# SCH_MicrowaveResistiveKeyb_2025-11-10.net
KiCad netlist of a schematic drawn in EasyEDA
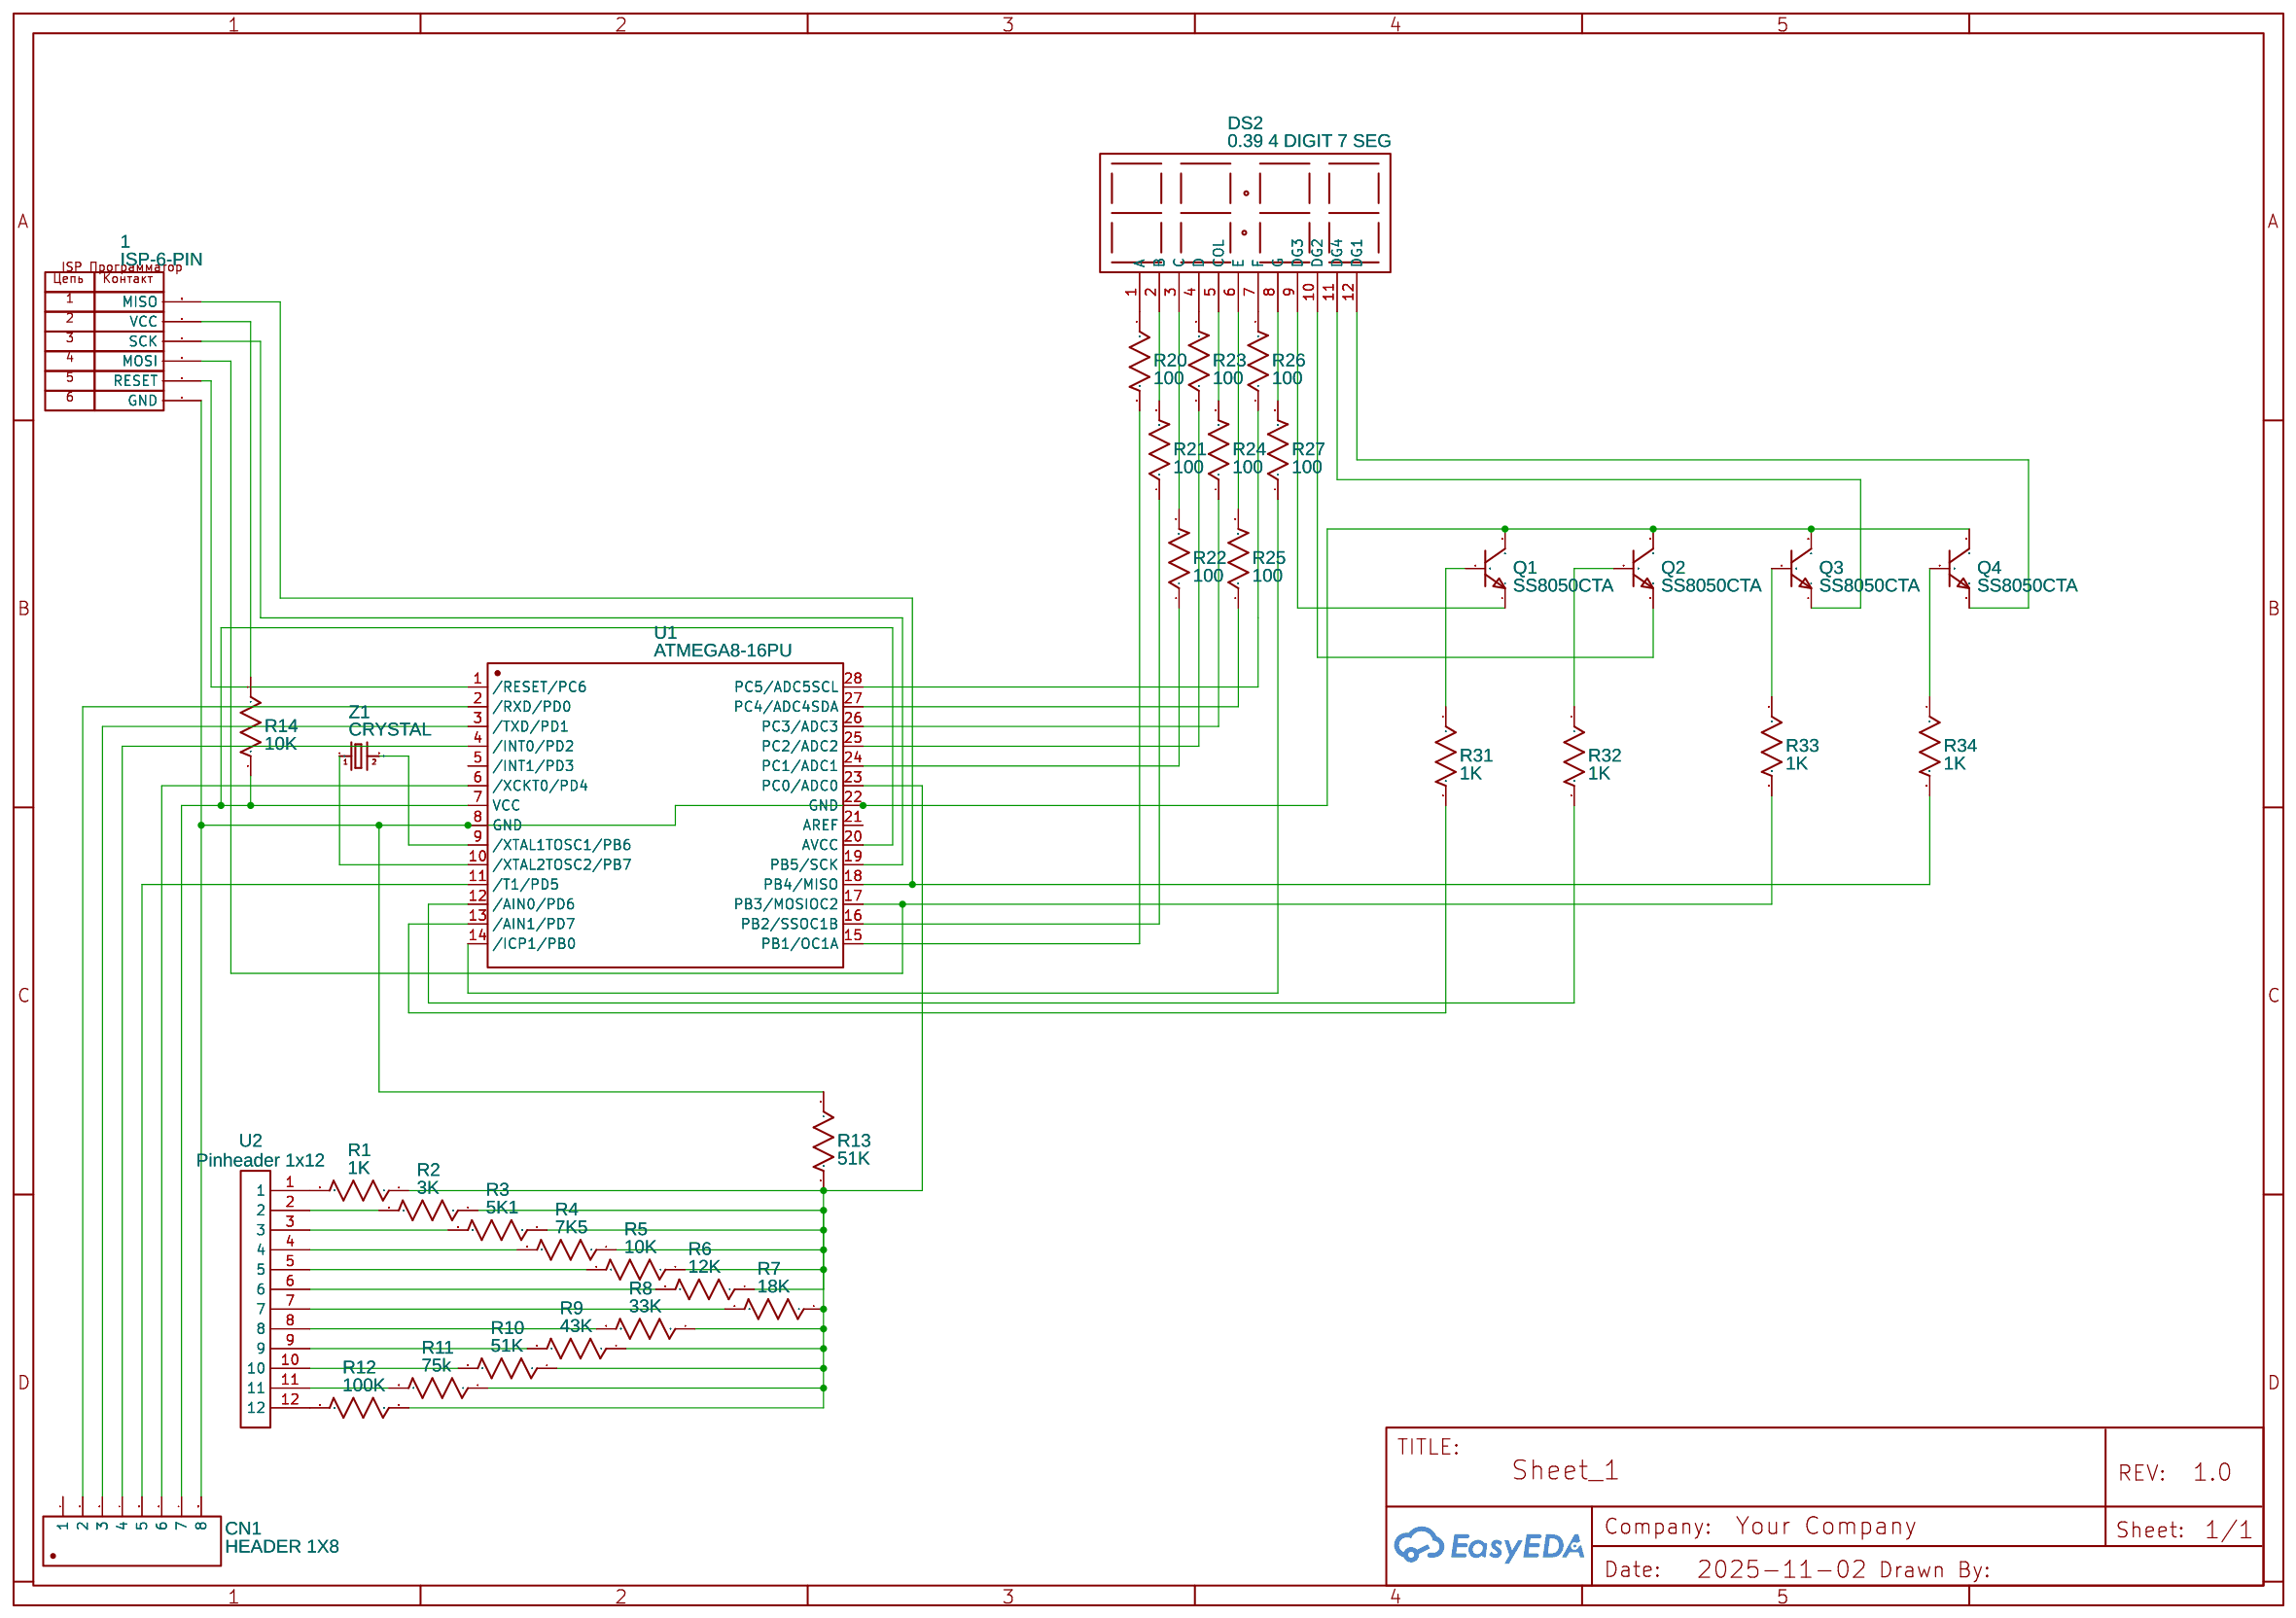
[diagram p0: schematic sheet]

(export (version "E")
  (design (tool "Eeschema 10.0.6"))
  (components
    (comp (ref "1") (value "ISP-6-PIN") (libsource (lib "") (part "ISP-6-PIN")))
    (comp (ref "CN1") (value "HEADER 1X8") (libsource (lib "") (part "HEADER 1X8")))
    (comp (ref "DS2")
      (value "0.39 4 DIGIT 7 SEG")
      (fields
        (field (name "Manufacturer Part") "0.39 Inch 4 Digit Common Anode 7 Segment Display Clock")
        (field (name "Manufacturer") "TAKAMISAWA")
      )
      (libsource (lib "") (part "0.39 4 DIGIT 7 SEG"))
    )
    (comp (ref "Q1")
      (value "SS8050CTA")
      (fields (field (name "Manufacturer") "onsemi(安森美)"))
      (libsource (lib "") (part "SS8050CTA"))
    )
    (comp (ref "Q2")
      (value "SS8050CTA")
      (fields (field (name "Manufacturer") "onsemi(安森美)"))
      (libsource (lib "") (part "SS8050CTA"))
    )
    (comp (ref "Q3")
      (value "SS8050CTA")
      (fields (field (name "Manufacturer") "onsemi(安森美)"))
      (libsource (lib "") (part "SS8050CTA"))
    )
    (comp (ref "Q4")
      (value "SS8050CTA")
      (fields (field (name "Manufacturer") "onsemi(安森美)"))
      (libsource (lib "") (part "SS8050CTA"))
    )
    (comp (ref "R1") (value "1K") (libsource (lib "") (part "CRCW060323K2FKEA")))
    (comp (ref "R2") (value "3K") (libsource (lib "") (part "CRCW060323K2FKEA")))
    (comp (ref "R3") (value "5K1") (libsource (lib "") (part "CRCW060323K2FKEA")))
    (comp (ref "R4") (value "7K5") (libsource (lib "") (part "CRCW060323K2FKEA")))
    (comp (ref "R5") (value "10K") (libsource (lib "") (part "CRCW060323K2FKEA")))
    (comp (ref "R6") (value "12K") (libsource (lib "") (part "CRCW060323K2FKEA")))
    (comp (ref "R7") (value "18K") (libsource (lib "") (part "CRCW060323K2FKEA")))
    (comp (ref "R8") (value "33K") (libsource (lib "") (part "CRCW060323K2FKEA")))
    (comp (ref "R9") (value "43K") (libsource (lib "") (part "CRCW060323K2FKEA")))
    (comp (ref "R10") (value "51K") (libsource (lib "") (part "CRCW060323K2FKEA")))
    (comp (ref "R11") (value "75k") (libsource (lib "") (part "CRCW060323K2FKEA")))
    (comp (ref "R12") (value "100K") (libsource (lib "") (part "CRCW060323K2FKEA")))
    (comp (ref "R13") (value "51K") (libsource (lib "") (part "CRCW060323K2FKEA_2")))
    (comp (ref "R14") (value "10K") (libsource (lib "") (part "CRCW060323K2FKEA_2")))
    (comp (ref "R20") (value "100") (libsource (lib "") (part "CRCW060323K2FKEA_2")))
    (comp (ref "R21") (value "100") (libsource (lib "") (part "CRCW060323K2FKEA_1")))
    (comp (ref "R22") (value "100") (libsource (lib "") (part "CRCW060323K2FKEA_1")))
    (comp (ref "R23") (value "100") (libsource (lib "") (part "CRCW060323K2FKEA_1")))
    (comp (ref "R24") (value "100") (libsource (lib "") (part "CRCW060323K2FKEA_1")))
    (comp (ref "R25") (value "100") (libsource (lib "") (part "CRCW060323K2FKEA_1")))
    (comp (ref "R26") (value "100") (libsource (lib "") (part "CRCW060323K2FKEA_1")))
    (comp (ref "R27") (value "100") (libsource (lib "") (part "CRCW060323K2FKEA_1")))
    (comp (ref "R31") (value "1K") (libsource (lib "") (part "CRCW060323K2FKEA_2")))
    (comp (ref "R32") (value "1K") (libsource (lib "") (part "CRCW060323K2FKEA_2")))
    (comp (ref "R33") (value "1K") (libsource (lib "") (part "CRCW060323K2FKEA_2")))
    (comp (ref "R34") (value "1K") (libsource (lib "") (part "CRCW060323K2FKEA_2")))
    (comp (ref "U1")
      (value "ATMEGA8-16PU")
      (fields (field (name "Manufacturer") "MICROCHIP(美国微芯)"))
      (libsource (lib "") (part "ATMEGA8-16PU"))
    )
    (comp (ref "U2") (value "Pinheader 1x12") (libsource (lib "") (part "Pinheader 1x12")))
    (comp (ref "Z1") (value "CRYSTAL") (libsource (lib "") (part "CRYSTAL")))
  )
  (nets
    (net (code "1") (name "Net-(1-GND)") (class "Default")
      (node (ref "1") (pin "P$6") (pinfunction "GND_P$6") (pintype "bidirectional"))
      (node (ref "CN1") (pin "8") (pinfunction "8_8") (pintype "unspecified"))
      (node (ref "Q1") (pin "3") (pinfunction "C_3") (pintype "unspecified"))
      (node (ref "Q2") (pin "3") (pinfunction "C_3") (pintype "unspecified"))
      (node (ref "Q3") (pin "3") (pinfunction "C_3") (pintype "unspecified"))
      (node (ref "Q4") (pin "3") (pinfunction "C_3") (pintype "unspecified"))
      (node (ref "R13") (pin "1") (pinfunction "1_1") (pintype "unspecified"))
      (node (ref "U1") (pin "22") (pinfunction "GND_22") (pintype "unspecified"))
      (node (ref "U1") (pin "8") (pinfunction "GND_8") (pintype "unspecified"))
    )
    (net (code "2") (name "Net-(1-MISO)") (class "Default")
      (node (ref "1") (pin "P$1") (pinfunction "MISO_P$1") (pintype "bidirectional"))
      (node (ref "R34") (pin "2") (pinfunction "2_2") (pintype "unspecified"))
      (node (ref "U1") (pin "18") (pinfunction "PB4/MISO_18") (pintype "unspecified"))
    )
    (net (code "3") (name "Net-(1-MOSI)") (class "Default")
      (node (ref "1") (pin "P$4") (pinfunction "MOSI_P$4") (pintype "bidirectional"))
      (node (ref "R33") (pin "2") (pinfunction "2_2") (pintype "unspecified"))
      (node (ref "U1") (pin "17") (pinfunction "PB3/MOSIOC2_17") (pintype "unspecified"))
    )
    (net (code "4") (name "Net-(1-RESET)") (class "Default")
      (node (ref "1") (pin "P$5") (pinfunction "RESET_P$5") (pintype "bidirectional"))
      (node (ref "U1") (pin "1") (pinfunction "/RESET/PC6_1") (pintype "unspecified"))
    )
    (net (code "5") (name "Net-(1-SCK)") (class "Default")
      (node (ref "1") (pin "P$3") (pinfunction "SCK_P$3") (pintype "bidirectional"))
      (node (ref "U1") (pin "19") (pinfunction "PB5/SCK_19") (pintype "unspecified"))
    )
    (net (code "6") (name "Net-(1-VCC)") (class "Default")
      (node (ref "1") (pin "P$2") (pinfunction "VCC_P$2") (pintype "bidirectional"))
      (node (ref "R14") (pin "1") (pinfunction "1_1") (pintype "unspecified"))
    )
    (net (code "7") (name "Net-(DS2-A)") (class "Default")
      (node (ref "DS2") (pin "1") (pinfunction "A_1") (pintype "unspecified"))
      (node (ref "R20") (pin "1") (pinfunction "1_1") (pintype "unspecified"))
    )
    (net (code "8") (name "Net-(DS2-B)") (class "Default")
      (node (ref "DS2") (pin "2") (pinfunction "B_2") (pintype "unspecified"))
      (node (ref "R21") (pin "2") (pinfunction "2_2") (pintype "unspecified"))
    )
    (net (code "9") (name "Net-(DS2-C)") (class "Default")
      (node (ref "DS2") (pin "3") (pinfunction "C_3") (pintype "unspecified"))
      (node (ref "R22") (pin "2") (pinfunction "2_2") (pintype "unspecified"))
    )
    (net (code "10") (name "Net-(DS2-COL)") (class "Default")
      (node (ref "DS2") (pin "5") (pinfunction "COL_5") (pintype "unspecified"))
      (node (ref "R24") (pin "2") (pinfunction "2_2") (pintype "unspecified"))
    )
    (net (code "11") (name "Net-(DS2-D)") (class "Default")
      (node (ref "DS2") (pin "4") (pinfunction "D_4") (pintype "unspecified"))
      (node (ref "R23") (pin "2") (pinfunction "2_2") (pintype "unspecified"))
    )
    (net (code "12") (name "Net-(DS2-DG1)") (class "Default")
      (node (ref "DS2") (pin "12") (pinfunction "DG1_12") (pintype "unspecified"))
      (node (ref "Q4") (pin "1") (pinfunction "E_1") (pintype "unspecified"))
    )
    (net (code "13") (name "Net-(DS2-DG2)") (class "Default")
      (node (ref "DS2") (pin "10") (pinfunction "DG2_10") (pintype "unspecified"))
      (node (ref "Q2") (pin "1") (pinfunction "E_1") (pintype "unspecified"))
    )
    (net (code "14") (name "Net-(DS2-DG3)") (class "Default")
      (node (ref "DS2") (pin "9") (pinfunction "DG3_9") (pintype "unspecified"))
      (node (ref "Q1") (pin "1") (pinfunction "E_1") (pintype "unspecified"))
    )
    (net (code "15") (name "Net-(DS2-DG4)") (class "Default")
      (node (ref "DS2") (pin "11") (pinfunction "DG4_11") (pintype "unspecified"))
      (node (ref "Q3") (pin "1") (pinfunction "E_1") (pintype "unspecified"))
    )
    (net (code "16") (name "Net-(DS2-E)") (class "Default")
      (node (ref "DS2") (pin "6") (pinfunction "E_6") (pintype "unspecified"))
      (node (ref "R25") (pin "2") (pinfunction "2_2") (pintype "unspecified"))
    )
    (net (code "17") (name "Net-(DS2-F)") (class "Default")
      (node (ref "DS2") (pin "7") (pinfunction "F_7") (pintype "unspecified"))
      (node (ref "R26") (pin "2") (pinfunction "2_2") (pintype "unspecified"))
    )
    (net (code "18") (name "Net-(DS2-G)") (class "Default")
      (node (ref "DS2") (pin "8") (pinfunction "G_8") (pintype "unspecified"))
      (node (ref "R27") (pin "2") (pinfunction "2_2") (pintype "unspecified"))
    )
    (net (code "19") (name "Net-(Q1-B)") (class "Default")
      (node (ref "Q1") (pin "2") (pinfunction "B_2") (pintype "unspecified"))
      (node (ref "R31") (pin "1") (pinfunction "1_1") (pintype "unspecified"))
    )
    (net (code "20") (name "Net-(Q2-B)") (class "Default")
      (node (ref "Q2") (pin "2") (pinfunction "B_2") (pintype "unspecified"))
      (node (ref "R32") (pin "1") (pinfunction "1_1") (pintype "unspecified"))
    )
    (net (code "21") (name "Net-(Q3-B)") (class "Default")
      (node (ref "Q3") (pin "2") (pinfunction "B_2") (pintype "unspecified"))
      (node (ref "R33") (pin "1") (pinfunction "1_1") (pintype "unspecified"))
    )
    (net (code "22") (name "Net-(Q4-B)") (class "Default")
      (node (ref "Q4") (pin "2") (pinfunction "B_2") (pintype "unspecified"))
      (node (ref "R34") (pin "1") (pinfunction "1_1") (pintype "unspecified"))
    )
    (net (code "23") (name "Net-(R1-Pad2)") (class "Default")
      (node (ref "R1") (pin "2") (pinfunction "2_2") (pintype "unspecified"))
      (node (ref "U2") (pin "1") (pinfunction "1_1") (pintype "unspecified"))
    )
    (net (code "24") (name "Net-(R2-Pad2)") (class "Default")
      (node (ref "R2") (pin "2") (pinfunction "2_2") (pintype "unspecified"))
      (node (ref "U2") (pin "2") (pinfunction "2_2") (pintype "unspecified"))
    )
    (net (code "25") (name "Net-(R3-Pad2)") (class "Default")
      (node (ref "R3") (pin "2") (pinfunction "2_2") (pintype "unspecified"))
      (node (ref "U2") (pin "3") (pinfunction "3_3") (pintype "unspecified"))
    )
    (net (code "26") (name "Net-(R4-Pad2)") (class "Default")
      (node (ref "R4") (pin "2") (pinfunction "2_2") (pintype "unspecified"))
      (node (ref "U2") (pin "4") (pinfunction "4_4") (pintype "unspecified"))
    )
    (net (code "27") (name "Net-(R5-Pad2)") (class "Default")
      (node (ref "R5") (pin "2") (pinfunction "2_2") (pintype "unspecified"))
      (node (ref "U2") (pin "5") (pinfunction "5_5") (pintype "unspecified"))
    )
    (net (code "28") (name "Net-(R6-Pad2)") (class "Default")
      (node (ref "R6") (pin "2") (pinfunction "2_2") (pintype "unspecified"))
      (node (ref "U2") (pin "6") (pinfunction "6_6") (pintype "unspecified"))
    )
    (net (code "29") (name "Net-(R7-Pad2)") (class "Default")
      (node (ref "R7") (pin "2") (pinfunction "2_2") (pintype "unspecified"))
      (node (ref "U2") (pin "7") (pinfunction "7_7") (pintype "unspecified"))
    )
    (net (code "30") (name "Net-(R8-Pad2)") (class "Default")
      (node (ref "R8") (pin "2") (pinfunction "2_2") (pintype "unspecified"))
      (node (ref "U2") (pin "8") (pinfunction "8_8") (pintype "unspecified"))
    )
    (net (code "31") (name "Net-(R9-Pad2)") (class "Default")
      (node (ref "R9") (pin "2") (pinfunction "2_2") (pintype "unspecified"))
      (node (ref "U2") (pin "9") (pinfunction "9_9") (pintype "unspecified"))
    )
    (net (code "32") (name "Net-(R10-Pad2)") (class "Default")
      (node (ref "R10") (pin "2") (pinfunction "2_2") (pintype "unspecified"))
      (node (ref "U2") (pin "10") (pinfunction "10_10") (pintype "unspecified"))
    )
    (net (code "33") (name "Net-(R11-Pad2)") (class "Default")
      (node (ref "R11") (pin "2") (pinfunction "2_2") (pintype "unspecified"))
      (node (ref "U2") (pin "11") (pinfunction "11_11") (pintype "unspecified"))
    )
    (net (code "34") (name "Net-(R12-Pad2)") (class "Default")
      (node (ref "R12") (pin "2") (pinfunction "2_2") (pintype "unspecified"))
      (node (ref "U2") (pin "12") (pinfunction "12_12") (pintype "unspecified"))
    )
    (net (code "35") (name "Net-(U1-AVCC)") (class "Default")
      (node (ref "CN1") (pin "7") (pinfunction "7_7") (pintype "unspecified"))
      (node (ref "R14") (pin "2") (pinfunction "2_2") (pintype "unspecified"))
      (node (ref "U1") (pin "20") (pinfunction "AVCC_20") (pintype "unspecified"))
      (node (ref "U1") (pin "7") (pinfunction "VCC_7") (pintype "unspecified"))
    )
    (net (code "36") (name "Net-(U1-PB1{slash}OC1A)") (class "Default")
      (node (ref "R20") (pin "2") (pinfunction "2_2") (pintype "unspecified"))
      (node (ref "U1") (pin "15") (pinfunction "PB1/OC1A_15") (pintype "unspecified"))
    )
    (net (code "37") (name "Net-(U1-PB2{slash}SSOC1B)") (class "Default")
      (node (ref "R21") (pin "1") (pinfunction "1_1") (pintype "unspecified"))
      (node (ref "U1") (pin "16") (pinfunction "PB2/SSOC1B_16") (pintype "unspecified"))
    )
    (net (code "38") (name "Net-(U1-PC0{slash}ADC0)") (class "Default")
      (node (ref "R1") (pin "1") (pinfunction "1_1") (pintype "unspecified"))
      (node (ref "R10") (pin "1") (pinfunction "1_1") (pintype "unspecified"))
      (node (ref "R11") (pin "1") (pinfunction "1_1") (pintype "unspecified"))
      (node (ref "R12") (pin "1") (pinfunction "1_1") (pintype "unspecified"))
      (node (ref "R13") (pin "2") (pinfunction "2_2") (pintype "unspecified"))
      (node (ref "R2") (pin "1") (pinfunction "1_1") (pintype "unspecified"))
      (node (ref "R3") (pin "1") (pinfunction "1_1") (pintype "unspecified"))
      (node (ref "R4") (pin "1") (pinfunction "1_1") (pintype "unspecified"))
      (node (ref "R5") (pin "1") (pinfunction "1_1") (pintype "unspecified"))
      (node (ref "R6") (pin "1") (pinfunction "1_1") (pintype "unspecified"))
      (node (ref "R7") (pin "1") (pinfunction "1_1") (pintype "unspecified"))
      (node (ref "R8") (pin "1") (pinfunction "1_1") (pintype "unspecified"))
      (node (ref "R9") (pin "1") (pinfunction "1_1") (pintype "unspecified"))
      (node (ref "U1") (pin "23") (pinfunction "PC0/ADC0_23") (pintype "unspecified"))
    )
    (net (code "39") (name "Net-(U1-PC1{slash}ADC1)") (class "Default")
      (node (ref "R22") (pin "1") (pinfunction "1_1") (pintype "unspecified"))
      (node (ref "U1") (pin "24") (pinfunction "PC1/ADC1_24") (pintype "unspecified"))
    )
    (net (code "40") (name "Net-(U1-PC2{slash}ADC2)") (class "Default")
      (node (ref "R23") (pin "1") (pinfunction "1_1") (pintype "unspecified"))
      (node (ref "U1") (pin "25") (pinfunction "PC2/ADC2_25") (pintype "unspecified"))
    )
    (net (code "41") (name "Net-(U1-PC3{slash}ADC3)") (class "Default")
      (node (ref "R24") (pin "1") (pinfunction "1_1") (pintype "unspecified"))
      (node (ref "U1") (pin "26") (pinfunction "PC3/ADC3_26") (pintype "unspecified"))
    )
    (net (code "42") (name "Net-(U1-PC4{slash}ADC4SDA)") (class "Default")
      (node (ref "R25") (pin "1") (pinfunction "1_1") (pintype "unspecified"))
      (node (ref "U1") (pin "27") (pinfunction "PC4/ADC4SDA_27") (pintype "unspecified"))
    )
    (net (code "43") (name "Net-(U1-PC5{slash}ADC5SCL)") (class "Default")
      (node (ref "R26") (pin "1") (pinfunction "1_1") (pintype "unspecified"))
      (node (ref "U1") (pin "28") (pinfunction "PC5/ADC5SCL_28") (pintype "unspecified"))
    )
    (net (code "44") (name "Net-(U1-{slash}AIN0{slash}PD6)") (class "Default")
      (node (ref "R32") (pin "2") (pinfunction "2_2") (pintype "unspecified"))
      (node (ref "U1") (pin "12") (pinfunction "/AIN0/PD6_12") (pintype "unspecified"))
    )
    (net (code "45") (name "Net-(U1-{slash}AIN1{slash}PD7)") (class "Default")
      (node (ref "R31") (pin "2") (pinfunction "2_2") (pintype "unspecified"))
      (node (ref "U1") (pin "13") (pinfunction "/AIN1/PD7_13") (pintype "unspecified"))
    )
    (net (code "46") (name "Net-(U1-{slash}ICP1{slash}PB0)") (class "Default")
      (node (ref "R27") (pin "1") (pinfunction "1_1") (pintype "unspecified"))
      (node (ref "U1") (pin "14") (pinfunction "/ICP1/PB0_14") (pintype "unspecified"))
    )
    (net (code "47") (name "Net-(U1-{slash}INT0{slash}PD2)") (class "Default")
      (node (ref "CN1") (pin "4") (pinfunction "4_4") (pintype "unspecified"))
      (node (ref "U1") (pin "4") (pinfunction "/INT0/PD2_4") (pintype "unspecified"))
    )
    (net (code "48") (name "Net-(U1-{slash}RXD{slash}PD0)") (class "Default")
      (node (ref "CN1") (pin "2") (pinfunction "2_2") (pintype "unspecified"))
      (node (ref "U1") (pin "2") (pinfunction "/RXD/PD0_2") (pintype "unspecified"))
    )
    (net (code "49") (name "Net-(U1-{slash}T1{slash}PD5)") (class "Default")
      (node (ref "CN1") (pin "5") (pinfunction "5_5") (pintype "unspecified"))
      (node (ref "U1") (pin "11") (pinfunction "/T1/PD5_11") (pintype "unspecified"))
    )
    (net (code "50") (name "Net-(U1-{slash}TXD{slash}PD1)") (class "Default")
      (node (ref "CN1") (pin "3") (pinfunction "3_3") (pintype "unspecified"))
      (node (ref "U1") (pin "3") (pinfunction "/TXD/PD1_3") (pintype "unspecified"))
    )
    (net (code "51") (name "Net-(U1-{slash}XCKT0{slash}PD4)") (class "Default")
      (node (ref "CN1") (pin "6") (pinfunction "6_6") (pintype "unspecified"))
      (node (ref "U1") (pin "6") (pinfunction "/XCKT0/PD4_6") (pintype "unspecified"))
    )
    (net (code "52") (name "Net-(U1-{slash}XTAL1TOSC1{slash}PB6)") (class "Default")
      (node (ref "U1") (pin "9") (pinfunction "/XTAL1TOSC1/PB6_9") (pintype "unspecified"))
      (node (ref "Z1") (pin "2") (pinfunction "2_2") (pintype "bidirectional"))
    )
    (net (code "53") (name "Net-(U1-{slash}XTAL2TOSC2{slash}PB7)") (class "Default")
      (node (ref "U1") (pin "10") (pinfunction "/XTAL2TOSC2/PB7_10") (pintype "unspecified"))
      (node (ref "Z1") (pin "1") (pinfunction "1_1") (pintype "bidirectional"))
    )
    (net (code "54") (name "unconnected-(CN1-Pad1)") (class "Default")
      (node (ref "CN1") (pin "1") (pinfunction "1_1") (pintype "unspecified"))
    )
    (net (code "55") (name "unconnected-(U1-AREF-Pad21)") (class "Default")
      (node (ref "U1") (pin "21") (pinfunction "AREF_21") (pintype "unspecified"))
    )
    (net (code "56") (name "unconnected-(U1-{slash}INT1{slash}PD3-Pad5)") (class "Default")
      (node (ref "U1") (pin "5") (pinfunction "/INT1/PD3_5") (pintype "unspecified"))
    )
  )
)
